# DRV10975_3-ph_Sensorless_BLDC_Motor_Driv.net
KiCad netlist of a schematic drawn in Altium Designer
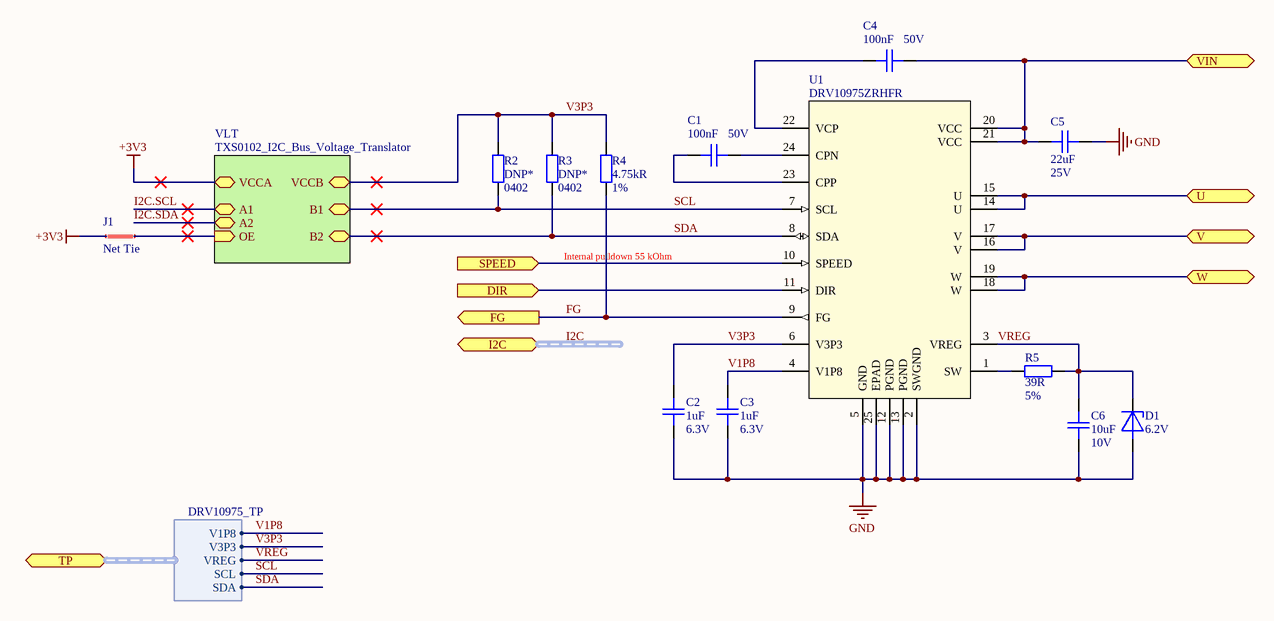
[diagram p0: DRV10975 3-ph Sensorless BLDC Motor Driver.SchDoc]

(export (version "E")
  (design (tool "Eeschema 10.0.6"))
  (components
    (comp (ref "C1")
      (value "CAP CER 0.1UF 50V X7R 0402")
      (footprint "C0402")
      (description "0.1µF ±10% 50V Ceramic Capacitor X7R 0402 (1005 Metric)")
      (fields
        (field (name "MANUFACTURER") "TDK")
        (field (name "MANUFACTURER PART NUMBER") "CGA2B3X7R1H104K050BB")
        (field (name "CAPACITANCE") "100nF")
        (field (name "VOLTAGE") "50V")
      )
      (libsource (lib "capacitors_smd") (part "CAP CER 0.1UF 50V X7R 0402"))
    )
    (comp (ref "C2")
      (value "CAP CER 1UF 6.3V X5R 0402")
      (footprint "C0402")
      (description "1µF ±10% 6.3V Ceramic Capacitor X5R 0402 (1005 Metric)")
      (fields
        (field (name "MANUFACTURER") "Yageo")
        (field (name "MANUFACTURER PART NUMBER") "CC0402KRX5R5BB105")
        (field (name "CAPACITANCE") "1uF")
        (field (name "VOLTAGE RATING") "6.3V")
      )
      (libsource (lib "capacitors_smd") (part "CAP CER 1UF 6.3V X5R 0402"))
    )
    (comp (ref "C3")
      (value "CAP CER 1UF 6.3V X5R 0402")
      (footprint "C0402")
      (description "1µF ±10% 6.3V Ceramic Capacitor X5R 0402 (1005 Metric)")
      (fields
        (field (name "MANUFACTURER") "Yageo")
        (field (name "MANUFACTURER PART NUMBER") "CC0402KRX5R5BB105")
        (field (name "CAPACITANCE") "1uF")
        (field (name "VOLTAGE RATING") "6.3V")
      )
      (libsource (lib "capacitors_smd") (part "CAP CER 1UF 6.3V X5R 0402"))
    )
    (comp (ref "C4")
      (value "CAP CER 0.1UF 50V X7R 0402")
      (footprint "C0402")
      (description "0.1µF ±10% 50V Ceramic Capacitor X7R 0402 (1005 Metric)")
      (fields
        (field (name "MANUFACTURER") "TDK")
        (field (name "MANUFACTURER PART NUMBER") "CGA2B3X7R1H104K050BB")
        (field (name "CAPACITANCE") "100nF")
        (field (name "VOLTAGE") "50V")
      )
      (libsource (lib "capacitors_smd") (part "CAP CER 0.1UF 50V X7R 0402"))
    )
    (comp (ref "C5")
      (value "CAP CER 22UF 25V X5R 0805")
      (footprint "C0805")
      (description "22µF ±20% 25V Ceramic Capacitor X5R 0805 (2012 Metric)")
      (fields
        (field (name "MANUFACTURER") "Yageo")
        (field (name "MANUFACTURER PART NUMBER") "CC0805MKX5R8BB226")
        (field (name "CAPACITANCE") "22uF")
        (field (name "VOLTAGE RATING") "25V")
      )
      (libsource (lib "capacitors_smd") (part "CAP CER 22UF 25V X5R 0805"))
    )
    (comp (ref "C6")
      (value "CAP CER 10uF X7R 10% 0805")
      (footprint "C0805")
      (description "Capacitor,10uF,10V,X7R,10%,0805,Murata")
      (fields
        (field (name "MANUFACTURER") "Murata")
        (field (name "MANUFACTURER PART NUMBER") "GRM21BR71A106KA73L")
        (field (name "CAPACITANCE") "10uF")
        (field (name "VOLTAGE RATING") "10V")
      )
      (libsource (lib "capacitors_smd") (part "CAP CER 10uF X7R 10% 0805"))
    )
    (comp (ref "D1")
      (value "Zener Diode 6.2V 2.5W ±5% Surface Mount SOD-123FL")
      (footprint "SOD-123FL")
      (fields
        (field (name "MANUFACTURER") "ON Semiconductor")
        (field (name "MANUFACTURER PART NUMBER") "1SMF5920BT1G")
        (field (name "TOLERANCE") "5%")
        (field (name "ZENER VOLTAGE") "6.2V")
      )
      (libsource (lib "diodes_zener") (part "DIODE ZENER 6.2V 2.5W SOD123FL"))
    )
    (comp (ref "J1")
      (value "Net Tie")
      (footprint "Net Tie 6x30mil")
      (libsource (lib "BLDC_Motor_Driver") (part "Net Tie Line"))
    )
    (comp (ref "R2")
      (value "DNP*")
      (footprint "R0402")
      (description "Placeholder for a 0402 resistor")
      (fields (field (name "CASE/PACKAGE") "0402"))
      (libsource (lib "resistors_smd") (part "RES SMD NO BOM 0402"))
    )
    (comp (ref "R3")
      (value "DNP*")
      (footprint "R0402")
      (description "Placeholder for a 0402 resistor")
      (fields (field (name "CASE/PACKAGE") "0402"))
      (libsource (lib "resistors_smd") (part "RES SMD NO BOM 0402"))
    )
    (comp (ref "R4")
      (value "RES SMD 4.75K OHM 1% 1/16W 0402")
      (footprint "R0402")
      (description "4.75 kOhms ±1% 0.063W, 1/16W Chip Resistor 0402 (1005 Metric) Moisture Resistant Thick Film")
      (fields
        (field (name "MANUFACTURER") "Yageo")
        (field (name "MANUFACTURER PART NUMBER") "RC0402FR-074K75P")
        (field (name "RESISTANCE") "4.75kR")
        (field (name "TOLERANCE") "1%")
      )
      (libsource (lib "resistors_smd") (part "RES SMD 4.75K OHM 1% 1/16W 0402"))
    )
    (comp (ref "R5")
      (value "RES SMD 39 OHM 1% 1/4W 1206")
      (footprint "R1206")
      (description "39 Ohms ±5% 0.25W, 1/4W Chip Resistor 1206 (3216 Metric) Moisture Resistant Thick Film")
      (fields
        (field (name "MANUFACTURER") "Yageo")
        (field (name "MANUFACTURER PART NUMBER") "RC1206JR-0739RL")
        (field (name "RESISTANCE") "39R")
        (field (name "TOLERANCE") "5%")
      )
      (libsource (lib "resistors_smd") (part "RES SMD 39 OHM 1% 1/4W 1206"))
    )
    (comp (ref "U1")
      (value "DRV10975ZRHFR")
      (footprint "RHF24_2P65X3P65")
      (description "Multiphase Motor Driver Power MOSFET Analog, I²C, PWM 24-VQFN (5x4)")
      (fields (field (name "MANUFACTURER") "Texas Instruments"))
      (libsource (lib "BLDC_Moto_Driver") (part "IC DRV10975Z BLDC MOTOR DRIVER VQFN-24"))
    )
  )
  (nets
    (net (code "3") (name "+3V3") (class "Default") (node (ref "J1") (pin "1") (pintype "passive")))
    (net (code "4") (name "/DIR") (class "Default")
      (node (ref "U1") (pin "11") (pinfunction "DIR_11") (pintype "input"))
    )
    (net (code "5") (name "/FG") (class "Default")
      (node (ref "R4") (pin "2") (pinfunction "2_2") (pintype "passive"))
      (node (ref "U1") (pin "9") (pinfunction "FG_9") (pintype "output"))
    )
    (net (code "8") (name "/OE") (class "Default") (node (ref "J1") (pin "2") (pintype "passive")))
    (net (code "9") (name "/SCL") (class "Default")
      (node (ref "R2") (pin "1") (pinfunction "1_1") (pintype "passive"))
      (node (ref "U1") (pin "7") (pinfunction "SCL_7") (pintype "input"))
    )
    (net (code "10") (name "/SDA") (class "Default")
      (node (ref "R3") (pin "1") (pinfunction "1_1") (pintype "passive"))
      (node (ref "U1") (pin "8") (pinfunction "SDA_8") (pintype "bidirectional"))
    )
    (net (code "11") (name "/SPEED") (class "Default")
      (node (ref "U1") (pin "10") (pinfunction "SPEED_10") (pintype "input"))
    )
    (net (code "12") (name "/U") (class "Default")
      (node (ref "U1") (pin "14") (pinfunction "U_14") (pintype "power_in"))
      (node (ref "U1") (pin "15") (pinfunction "U_15") (pintype "power_in"))
    )
    (net (code "13") (name "/V") (class "Default")
      (node (ref "U1") (pin "16") (pinfunction "V_16") (pintype "power_in"))
      (node (ref "U1") (pin "17") (pinfunction "V_17") (pintype "power_in"))
    )
    (net (code "14") (name "/V1P8") (class "Default")
      (node (ref "C3") (pin "2") (pinfunction "2_2") (pintype "passive"))
      (node (ref "U1") (pin "4") (pinfunction "V1P8_4") (pintype "power_in"))
    )
    (net (code "15") (name "/V3P3") (class "Default")
      (node (ref "C2") (pin "2") (pinfunction "2_2") (pintype "passive"))
      (node (ref "R2") (pin "2") (pinfunction "2_2") (pintype "passive"))
      (node (ref "R3") (pin "2") (pinfunction "2_2") (pintype "passive"))
      (node (ref "R4") (pin "1") (pinfunction "1_1") (pintype "passive"))
      (node (ref "U1") (pin "6") (pinfunction "V3P3_6") (pintype "power_in"))
    )
    (net (code "16") (name "/VIN") (class "Default")
      (node (ref "C4") (pin "2") (pinfunction "2_2") (pintype "passive"))
      (node (ref "C5") (pin "1") (pinfunction "1_1") (pintype "passive"))
      (node (ref "U1") (pin "20") (pinfunction "VCC_20") (pintype "power_in"))
      (node (ref "U1") (pin "21") (pinfunction "VCC_21") (pintype "power_in"))
    )
    (net (code "17") (name "/VREG") (class "Default")
      (node (ref "C6") (pin "1") (pinfunction "1_1") (pintype "passive"))
      (node (ref "D1") (pin "1") (pinfunction "K_1") (pintype "passive"))
      (node (ref "R5") (pin "2") (pinfunction "2_2") (pintype "passive"))
      (node (ref "U1") (pin "3") (pinfunction "VREG_3") (pintype "power_in"))
    )
    (net (code "18") (name "/W") (class "Default")
      (node (ref "U1") (pin "18") (pinfunction "W_18") (pintype "power_in"))
      (node (ref "U1") (pin "19") (pinfunction "W_19") (pintype "power_in"))
    )
    (net (code "21") (name "GND") (class "Default")
      (node (ref "C2") (pin "1") (pinfunction "1_1") (pintype "passive"))
      (node (ref "C3") (pin "1") (pinfunction "1_1") (pintype "passive"))
      (node (ref "C5") (pin "2") (pinfunction "2_2") (pintype "passive"))
      (node (ref "C6") (pin "2") (pinfunction "2_2") (pintype "passive"))
      (node (ref "D1") (pin "2") (pinfunction "A_2") (pintype "passive"))
      (node (ref "U1") (pin "12") (pinfunction "PGND_12") (pintype "power_in"))
      (node (ref "U1") (pin "13") (pinfunction "PGND_13") (pintype "power_in"))
      (node (ref "U1") (pin "2") (pinfunction "SWGND_2") (pintype "power_in"))
      (node (ref "U1") (pin "25") (pinfunction "EPAD_25") (pintype "power_in"))
      (node (ref "U1") (pin "5") (pinfunction "GND_5") (pintype "power_in"))
    )
    (net (code "22") (name "Net-(U1-CPN)") (class "Default")
      (node (ref "C1") (pin "2") (pinfunction "2_2") (pintype "passive"))
      (node (ref "U1") (pin "24") (pinfunction "CPN_24") (pintype "power_in"))
    )
    (net (code "23") (name "Net-(U1-CPP)") (class "Default")
      (node (ref "C1") (pin "1") (pinfunction "1_1") (pintype "passive"))
      (node (ref "U1") (pin "23") (pinfunction "CPP_23") (pintype "power_in"))
    )
    (net (code "24") (name "Net-(U1-SW)") (class "Default")
      (node (ref "R5") (pin "1") (pinfunction "1_1") (pintype "passive"))
      (node (ref "U1") (pin "1") (pinfunction "SW_1") (pintype "power_in"))
    )
    (net (code "25") (name "Net-(U1-VCP)") (class "Default")
      (node (ref "C4") (pin "1") (pinfunction "1_1") (pintype "passive"))
      (node (ref "U1") (pin "22") (pinfunction "VCP_22") (pintype "power_in"))
    )
  )
)
